# IMU_CAN_Speed_Converter_Board_rev1.net
KiCad netlist of a schematic drawn in EAGLE
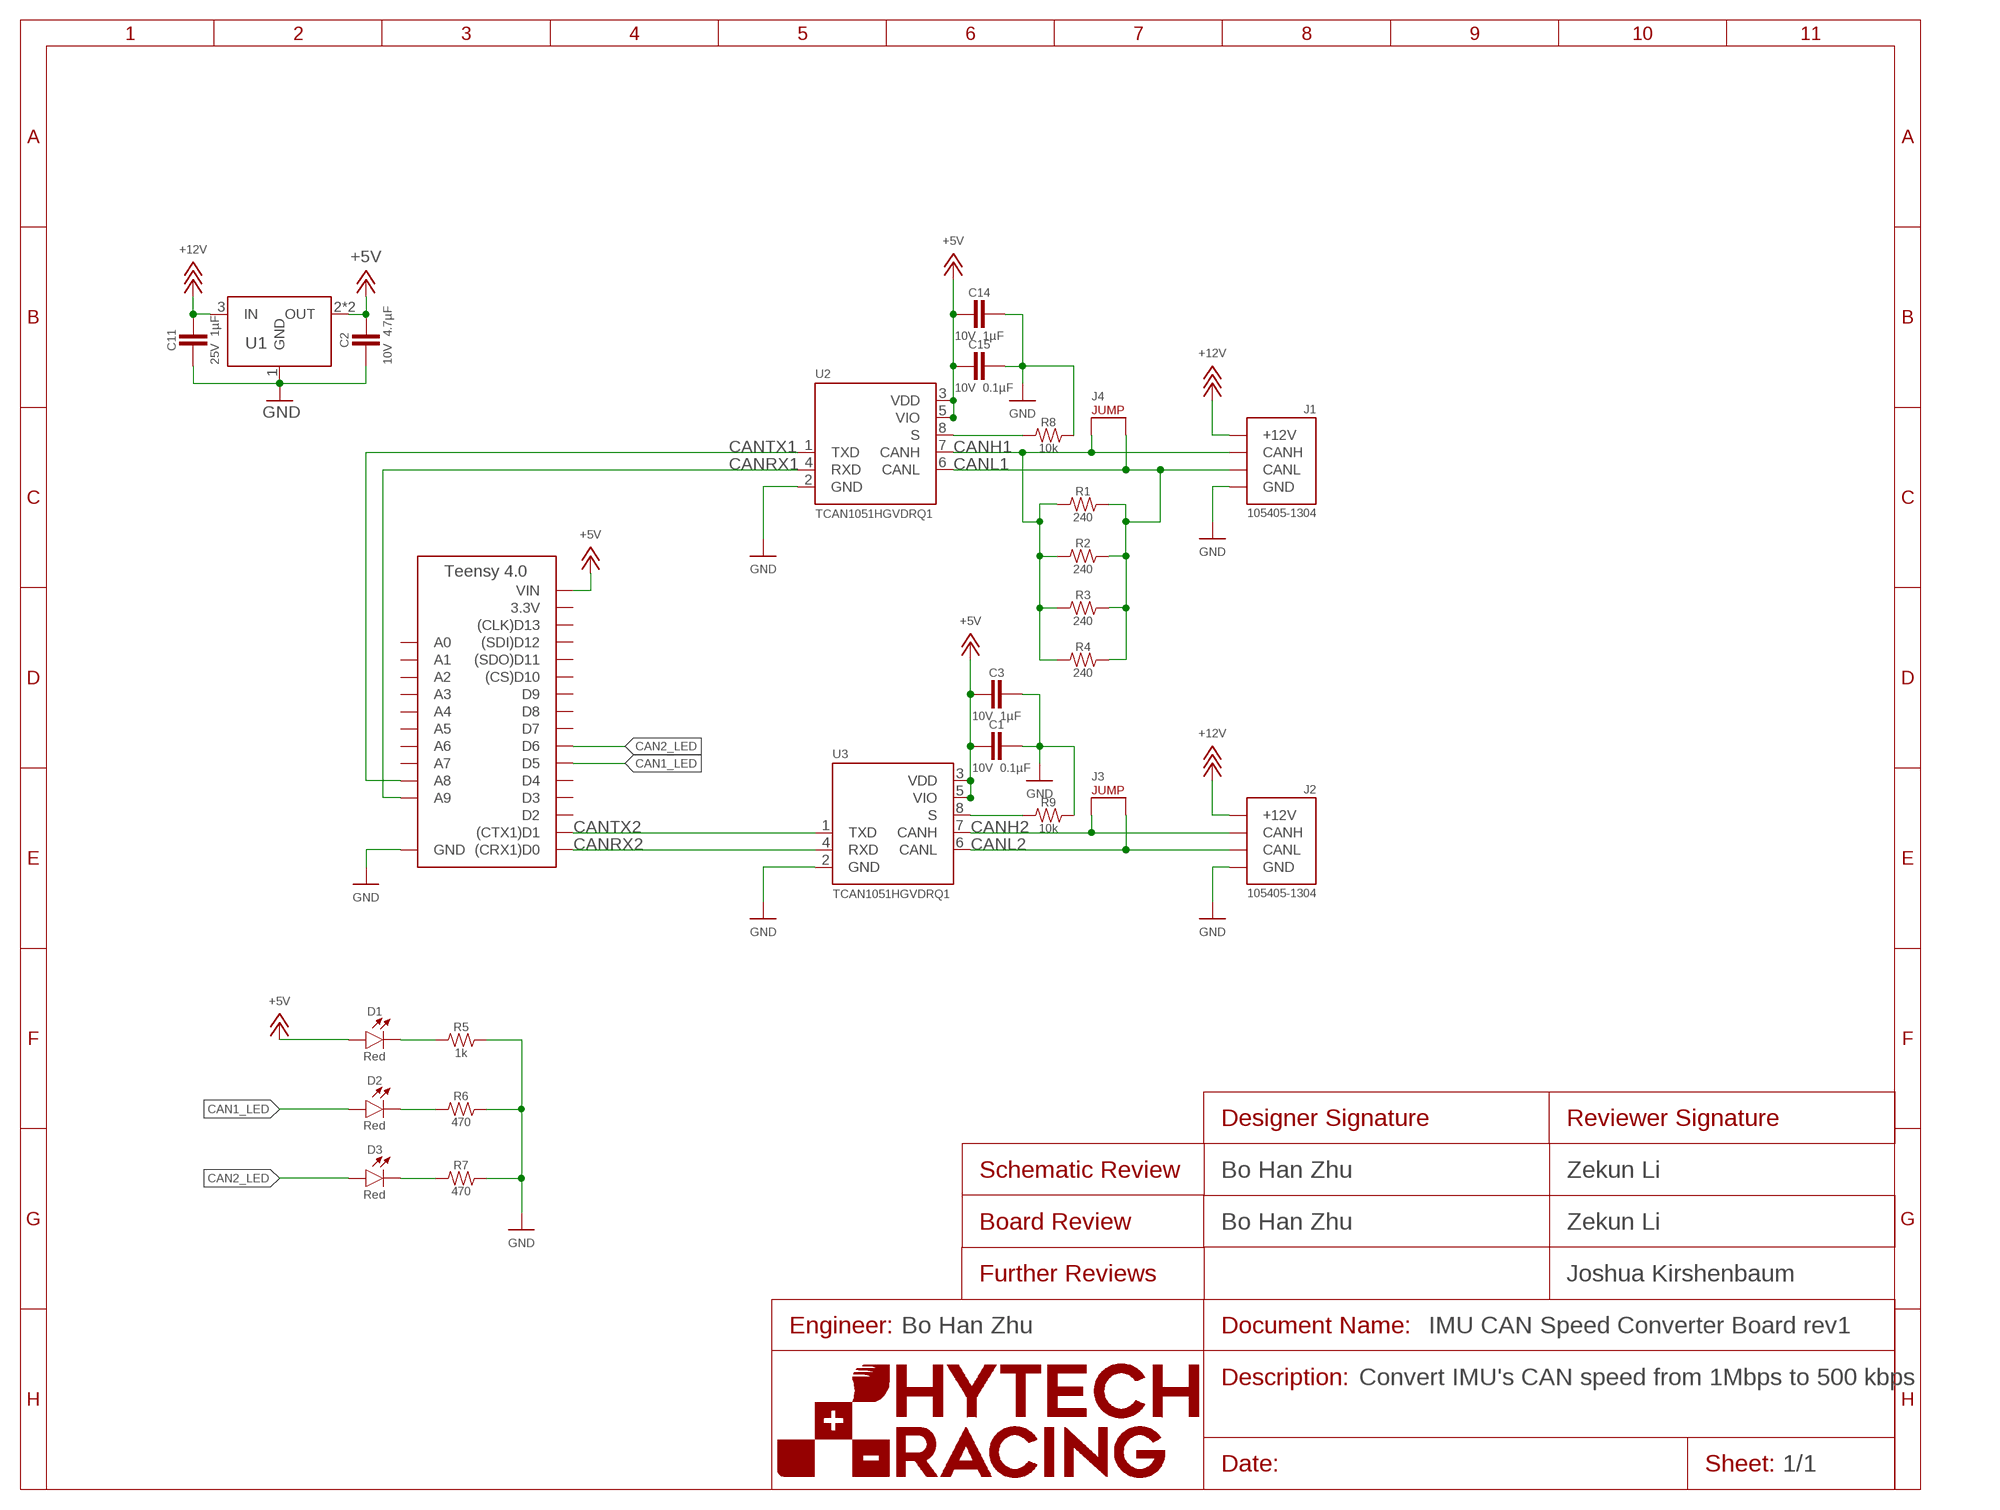
[diagram p0: schematic, sheet 1]

(export (version "E")
  (design (tool "Eeschema 10.0.6"))
  (components
    (comp (ref "A1")
      (value "TEENSY_4.0")
      (footprint "eagle-import:TEENSY_SHORT")
      (libsource (lib "eagle-import") (part "TEENSY_4.0"))
    )
    (comp (ref "C1")
      (value "CAPACITOR_0603_10V_0.1UF")
      (footprint "eagle-import:0603-CAP")
      (fields
        (field (name "CAPACITANCE") "0.1µF")
        (field (name "MANUFACTURER") "Vishay Vitramon")
        (field (name "MPN") "VJ0603Y104JXQPW1BC")
        (field (name "TOLERANCE") "5%")
        (field (name "VOLTAGE") "10V")
      )
      (libsource (lib "eagle-import") (part "CAPACITOR_?_060310V_0.1UF"))
    )
    (comp (ref "C2")
      (value "CAPACITOR_0603_10V_4.7UF")
      (footprint "eagle-import:0603-CAP")
      (fields
        (field (name "CAPACITANCE") "4.7µF")
        (field (name "MANUFACTURER") "Samsung Electro-Mechanics")
        (field (name "MPN") "CL10A475KP8NNNC")
        (field (name "TOLERANCE") "10%")
        (field (name "VOLTAGE") "10V")
      )
      (libsource (lib "eagle-import") (part "CAPACITOR_?_060310V_4.7UF"))
    )
    (comp (ref "C3")
      (value "CAPACITOR_0603_10V_1UF")
      (footprint "eagle-import:0603-CAP")
      (fields
        (field (name "CAPACITANCE") "1µF")
        (field (name "MANUFACTURER") "Yageo")
        (field (name "MPN") "CC0603KRX7R6BB105")
        (field (name "TOLERANCE") "10%")
        (field (name "VOLTAGE") "10V")
      )
      (libsource (lib "eagle-import") (part "CAPACITOR_?_060310V_1UF"))
    )
    (comp (ref "C11")
      (value "CAPACITOR_0603_25V_1UF")
      (footprint "eagle-import:0603-CAP")
      (fields
        (field (name "CAPACITANCE") "1µF")
        (field (name "MANUFACTURER") "Samsung Electro-Mechanics")
        (field (name "MPN") "CL10B105KA8NNNC")
        (field (name "TOLERANCE") "10%")
        (field (name "VOLTAGE") "25V")
      )
      (libsource (lib "eagle-import") (part "CAPACITOR_?_060325V_1UF"))
    )
    (comp (ref "C14")
      (value "CAPACITOR_0603_10V_1UF")
      (footprint "eagle-import:0603-CAP")
      (fields
        (field (name "CAPACITANCE") "1µF")
        (field (name "MANUFACTURER") "Yageo")
        (field (name "MPN") "CC0603KRX7R6BB105")
        (field (name "TOLERANCE") "10%")
        (field (name "VOLTAGE") "10V")
      )
      (libsource (lib "eagle-import") (part "CAPACITOR_?_060310V_1UF"))
    )
    (comp (ref "C15")
      (value "CAPACITOR_0603_10V_0.1UF")
      (footprint "eagle-import:0603-CAP")
      (fields
        (field (name "CAPACITANCE") "0.1µF")
        (field (name "MANUFACTURER") "Vishay Vitramon")
        (field (name "MPN") "VJ0603Y104JXQPW1BC")
        (field (name "TOLERANCE") "5%")
        (field (name "VOLTAGE") "10V")
      )
      (libsource (lib "eagle-import") (part "CAPACITOR_?_060310V_0.1UF"))
    )
    (comp (ref "D1")
      (value "LED_0603_RED")
      (footprint "eagle-import:0603-LED")
      (fields
        (field (name "COLOR") "Red")
        (field (name "MANUFACTURER") "Kingbright")
        (field (name "MPN") "APT1608SECK/J3-PRV")
      )
      (libsource (lib "eagle-import") (part "LED_?_0603RED"))
    )
    (comp (ref "D2")
      (value "LED_0603_RED")
      (footprint "eagle-import:0603-LED")
      (fields
        (field (name "COLOR") "Red")
        (field (name "MANUFACTURER") "Kingbright")
        (field (name "MPN") "APT1608SECK/J3-PRV")
      )
      (libsource (lib "eagle-import") (part "LED_?_0603RED"))
    )
    (comp (ref "D3")
      (value "LED_0603_RED")
      (footprint "eagle-import:0603-LED")
      (fields
        (field (name "COLOR") "Red")
        (field (name "MANUFACTURER") "Kingbright")
        (field (name "MPN") "APT1608SECK/J3-PRV")
      )
      (libsource (lib "eagle-import") (part "LED_?_0603RED"))
    )
    (comp (ref "J1")
      (value "CONNECTOR-CAN_NF_S_RA_BLACK")
      (footprint "eagle-import:MOLEX_NANOFIT_SMD_RIGHTANGLE_04")
      (fields (field (name "MANUFACTURER") "Molex") (field (name "MPN") "105405-1304"))
      (libsource (lib "eagle-import") (part "CONNECTOR-CAN_?_NF_S_RABLACK"))
    )
    (comp (ref "J2")
      (value "CONNECTOR-CAN_NF_S_RA_BLACK")
      (footprint "eagle-import:MOLEX_NANOFIT_SMD_RIGHTANGLE_04")
      (fields (field (name "MANUFACTURER") "Molex") (field (name "MPN") "105405-1304"))
      (libsource (lib "eagle-import") (part "CONNECTOR-CAN_?_NF_S_RABLACK"))
    )
    (comp (ref "J3")
      (value "JUMPER_1X02_")
      (footprint "eagle-import:1X02")
      (libsource (lib "eagle-import") (part "JUMPER_?_1X02"))
    )
    (comp (ref "J4")
      (value "JUMPER_1X02_")
      (footprint "eagle-import:1X02")
      (libsource (lib "eagle-import") (part "JUMPER_?_1X02"))
    )
    (comp (ref "R1")
      (value "RESISTOR_0603_240")
      (footprint "eagle-import:0603-RES")
      (fields
        (field (name "MANUFACTURER") "Yageo")
        (field (name "MPN") "RC0603FR-07240RL")
        (field (name "POWER") "0.1W")
        (field (name "RESISTANCE") "240")
      )
      (libsource (lib "eagle-import") (part "RESISTOR_?_0603240"))
    )
    (comp (ref "R2")
      (value "RESISTOR_0603_240")
      (footprint "eagle-import:0603-RES")
      (fields
        (field (name "MANUFACTURER") "Yageo")
        (field (name "MPN") "RC0603FR-07240RL")
        (field (name "POWER") "0.1W")
        (field (name "RESISTANCE") "240")
      )
      (libsource (lib "eagle-import") (part "RESISTOR_?_0603240"))
    )
    (comp (ref "R3")
      (value "RESISTOR_0603_240")
      (footprint "eagle-import:0603-RES")
      (fields
        (field (name "MANUFACTURER") "Yageo")
        (field (name "MPN") "RC0603FR-07240RL")
        (field (name "POWER") "0.1W")
        (field (name "RESISTANCE") "240")
      )
      (libsource (lib "eagle-import") (part "RESISTOR_?_0603240"))
    )
    (comp (ref "R4")
      (value "RESISTOR_0603_240")
      (footprint "eagle-import:0603-RES")
      (fields
        (field (name "MANUFACTURER") "Yageo")
        (field (name "MPN") "RC0603FR-07240RL")
        (field (name "POWER") "0.1W")
        (field (name "RESISTANCE") "240")
      )
      (libsource (lib "eagle-import") (part "RESISTOR_?_0603240"))
    )
    (comp (ref "R5")
      (value "RESISTOR_0603_1K")
      (footprint "eagle-import:0603-RES")
      (fields
        (field (name "MANUFACTURER") "Yageo")
        (field (name "MPN") "RC0603FR-071KL")
        (field (name "POWER") "0.1W")
        (field (name "RESISTANCE") "1k")
      )
      (libsource (lib "eagle-import") (part "RESISTOR_?_06031K"))
    )
    (comp (ref "R6")
      (value "RESISTOR_0603_470")
      (footprint "eagle-import:0603-RES")
      (fields
        (field (name "MANUFACTURER") "Panasonic Electronic Components")
        (field (name "MPN") "ERJ-PA3F4700V")
        (field (name "POWER") "0.25W")
        (field (name "RESISTANCE") "470")
      )
      (libsource (lib "eagle-import") (part "RESISTOR_?_0603470"))
    )
    (comp (ref "R7")
      (value "RESISTOR_0603_470")
      (footprint "eagle-import:0603-RES")
      (fields
        (field (name "MANUFACTURER") "Panasonic Electronic Components")
        (field (name "MPN") "ERJ-PA3F4700V")
        (field (name "POWER") "0.25W")
        (field (name "RESISTANCE") "470")
      )
      (libsource (lib "eagle-import") (part "RESISTOR_?_0603470"))
    )
    (comp (ref "R8")
      (value "RESISTOR_0603_10K")
      (footprint "eagle-import:0603-RES")
      (fields
        (field (name "MANUFACTURER") "Yageo")
        (field (name "MPN") "RC0603FR-0710KL")
        (field (name "POWER") "0.1W")
        (field (name "RESISTANCE") "10k")
      )
      (libsource (lib "eagle-import") (part "RESISTOR_?_060310K"))
    )
    (comp (ref "R9")
      (value "RESISTOR_0603_10K")
      (footprint "eagle-import:0603-RES")
      (fields
        (field (name "MANUFACTURER") "Yageo")
        (field (name "MPN") "RC0603FR-0710KL")
        (field (name "POWER") "0.1W")
        (field (name "RESISTANCE") "10k")
      )
      (libsource (lib "eagle-import") (part "RESISTOR_?_060310K"))
    )
    (comp (ref "U1")
      (value "VOLTAGE_REGULATOR_SOT223_5V")
      (footprint "eagle-import:SOT223")
      (fields (field (name "MANUFACTURER") "STMicroelectronics") (field (name "MPN") "LDL1117S50R"))
      (libsource (lib "eagle-import") (part "VOLTAGE_REGULATOR_?_SOT2235V"))
    )
    (comp (ref "U2")
      (value "TCAN1051HQV-Q1")
      (footprint "eagle-import:SOIC-08(NARROW,0.15_)")
      (fields (field (name "MANUFACTURER") "Texas Instruments") (field (name "MPN") "TCAN1051HGVDRQ1"))
      (libsource (lib "eagle-import") (part "TCAN1051V-Q1HQ"))
    )
    (comp (ref "U3")
      (value "TCAN1051HQV-Q1")
      (footprint "eagle-import:SOIC-08(NARROW,0.15_)")
      (fields (field (name "MANUFACTURER") "Texas Instruments") (field (name "MPN") "TCAN1051HGVDRQ1"))
      (libsource (lib "eagle-import") (part "TCAN1051V-Q1HQ"))
    )
  )
  (nets
    (net (code "1") (name "+5V") (class "Default")
      (node (ref "A1") (pin "VIN") (pinfunction "VIN_VIN") (pintype "power_in"))
      (node (ref "C1") (pin "2") (pinfunction "2_2") (pintype "passive"))
      (node (ref "C14") (pin "2") (pinfunction "2_2") (pintype "passive"))
      (node (ref "C15") (pin "2") (pinfunction "2_2") (pintype "passive"))
      (node (ref "C2") (pin "1") (pinfunction "1_1") (pintype "passive"))
      (node (ref "C3") (pin "2") (pinfunction "2_2") (pintype "passive"))
      (node (ref "D1") (pin "2") (pinfunction "A_2") (pintype "passive"))
      (node (ref "U1") (pin "2") (pinfunction "OUT_2") (pintype "power_in"))
      (node (ref "U1") (pin "4") (pinfunction "OUT_4") (pintype "power_in"))
      (node (ref "U2") (pin "3") (pinfunction "VDD_3") (pintype "power_in"))
      (node (ref "U2") (pin "5") (pinfunction "VIO_5") (pintype "power_in"))
      (node (ref "U3") (pin "3") (pinfunction "VDD_3") (pintype "power_in"))
      (node (ref "U3") (pin "5") (pinfunction "VIO_5") (pintype "power_in"))
    )
    (net (code "2") (name "+12V") (class "Default")
      (node (ref "C11") (pin "1") (pinfunction "1_1") (pintype "passive"))
      (node (ref "J1") (pin "1") (pinfunction "+12V_1") (pintype "power_in"))
      (node (ref "J2") (pin "1") (pinfunction "+12V_1") (pintype "power_in"))
      (node (ref "U1") (pin "3") (pinfunction "IN_3") (pintype "power_in"))
    )
    (net (code "3") (name "/3.3V") (class "Default")
      (node (ref "A1") (pin "3.3V") (pinfunction "3.3V_3.3V") (pintype "power_in"))
    )
    (net (code "4") (name "/CANH1") (class "Default")
      (node (ref "J1") (pin "4") (pinfunction "CANH_4") (pintype "bidirectional"))
      (node (ref "J4") (pin "1") (pinfunction "P$1_1") (pintype "passive"))
      (node (ref "R1") (pin "1") (pinfunction "1_1") (pintype "passive"))
      (node (ref "R2") (pin "1") (pinfunction "1_1") (pintype "passive"))
      (node (ref "R3") (pin "1") (pinfunction "1_1") (pintype "passive"))
      (node (ref "R4") (pin "1") (pinfunction "1_1") (pintype "passive"))
      (node (ref "U2") (pin "7") (pinfunction "CANH_7") (pintype "output"))
    )
    (net (code "5") (name "/CANH2") (class "Default")
      (node (ref "J2") (pin "4") (pinfunction "CANH_4") (pintype "bidirectional"))
      (node (ref "J3") (pin "1") (pinfunction "P$1_1") (pintype "passive"))
      (node (ref "U3") (pin "7") (pinfunction "CANH_7") (pintype "output"))
    )
    (net (code "6") (name "/CANL1") (class "Default")
      (node (ref "J1") (pin "3") (pinfunction "CANL_3") (pintype "bidirectional"))
      (node (ref "J4") (pin "2") (pinfunction "P$2_2") (pintype "passive"))
      (node (ref "R1") (pin "2") (pinfunction "2_2") (pintype "passive"))
      (node (ref "R2") (pin "2") (pinfunction "2_2") (pintype "passive"))
      (node (ref "R3") (pin "2") (pinfunction "2_2") (pintype "passive"))
      (node (ref "R4") (pin "2") (pinfunction "2_2") (pintype "passive"))
      (node (ref "U2") (pin "6") (pinfunction "CANL_6") (pintype "bidirectional"))
    )
    (net (code "7") (name "/CANL2") (class "Default")
      (node (ref "J2") (pin "3") (pinfunction "CANL_3") (pintype "bidirectional"))
      (node (ref "J3") (pin "2") (pinfunction "P$2_2") (pintype "passive"))
      (node (ref "U3") (pin "6") (pinfunction "CANL_6") (pintype "bidirectional"))
    )
    (net (code "8") (name "/CANRX1") (class "Default")
      (node (ref "A1") (pin "D23") (pinfunction "A9_D23") (pintype "bidirectional"))
      (node (ref "U2") (pin "4") (pinfunction "RXD_4") (pintype "output"))
    )
    (net (code "9") (name "/CANRX2") (class "Default")
      (node (ref "A1") (pin "D0") (pinfunction "(CRX1)D0_D0") (pintype "bidirectional"))
      (node (ref "U3") (pin "4") (pinfunction "RXD_4") (pintype "output"))
    )
    (net (code "10") (name "/CANTX1") (class "Default")
      (node (ref "A1") (pin "D22") (pinfunction "A8_D22") (pintype "bidirectional"))
      (node (ref "U2") (pin "1") (pinfunction "TXD_1") (pintype "input"))
    )
    (net (code "11") (name "/CANTX2") (class "Default")
      (node (ref "A1") (pin "D1") (pinfunction "(CTX1)D1_D1") (pintype "bidirectional"))
      (node (ref "U3") (pin "1") (pinfunction "TXD_1") (pintype "input"))
    )
    (net (code "12") (name "CAN1_LED") (class "Default")
      (node (ref "A1") (pin "D5") (pinfunction "D5_D5") (pintype "bidirectional"))
      (node (ref "D2") (pin "2") (pinfunction "A_2") (pintype "passive"))
    )
    (net (code "13") (name "CAN2_LED") (class "Default")
      (node (ref "A1") (pin "D6") (pinfunction "D6_D6") (pintype "bidirectional"))
      (node (ref "D3") (pin "2") (pinfunction "A_2") (pintype "passive"))
    )
    (net (code "14") (name "GND") (class "Default")
      (node (ref "A1") (pin "AGND/GND") (pinfunction "GND_AGND/GND") (pintype "power_in"))
      (node (ref "A1") (pin "GND") (pinfunction "GND_GND") (pintype "power_in"))
      (node (ref "C1") (pin "1") (pinfunction "1_1") (pintype "passive"))
      (node (ref "C11") (pin "2") (pinfunction "2_2") (pintype "passive"))
      (node (ref "C14") (pin "1") (pinfunction "1_1") (pintype "passive"))
      (node (ref "C15") (pin "1") (pinfunction "1_1") (pintype "passive"))
      (node (ref "C2") (pin "2") (pinfunction "2_2") (pintype "passive"))
      (node (ref "C3") (pin "1") (pinfunction "1_1") (pintype "passive"))
      (node (ref "J1") (pin "2") (pinfunction "GND_2") (pintype "power_in"))
      (node (ref "J2") (pin "2") (pinfunction "GND_2") (pintype "power_in"))
      (node (ref "R5") (pin "2") (pinfunction "2_2") (pintype "passive"))
      (node (ref "R6") (pin "2") (pinfunction "2_2") (pintype "passive"))
      (node (ref "R7") (pin "2") (pinfunction "2_2") (pintype "passive"))
      (node (ref "R8") (pin "2") (pinfunction "2_2") (pintype "passive"))
      (node (ref "R9") (pin "2") (pinfunction "2_2") (pintype "passive"))
      (node (ref "U1") (pin "1") (pinfunction "GND_1") (pintype "power_in"))
      (node (ref "U2") (pin "2") (pinfunction "GND_2") (pintype "power_in"))
      (node (ref "U3") (pin "2") (pinfunction "GND_2") (pintype "power_in"))
    )
    (net (code "15") (name "Net-(D1-C)") (class "Default")
      (node (ref "D1") (pin "1") (pinfunction "C_1") (pintype "passive"))
      (node (ref "R5") (pin "1") (pinfunction "1_1") (pintype "passive"))
    )
    (net (code "16") (name "Net-(D2-C)") (class "Default")
      (node (ref "D2") (pin "1") (pinfunction "C_1") (pintype "passive"))
      (node (ref "R6") (pin "1") (pinfunction "1_1") (pintype "passive"))
    )
    (net (code "17") (name "Net-(D3-C)") (class "Default")
      (node (ref "D3") (pin "1") (pinfunction "C_1") (pintype "passive"))
      (node (ref "R7") (pin "1") (pinfunction "1_1") (pintype "passive"))
    )
    (net (code "18") (name "Net-(U2-S)") (class "Default")
      (node (ref "R8") (pin "1") (pinfunction "1_1") (pintype "passive"))
      (node (ref "U2") (pin "8") (pinfunction "S_8") (pintype "input"))
    )
    (net (code "19") (name "Net-(U3-S)") (class "Default")
      (node (ref "R9") (pin "1") (pinfunction "1_1") (pintype "passive"))
      (node (ref "U3") (pin "8") (pinfunction "S_8") (pintype "input"))
    )
    (net (code "20") (name "unconnected-(A1-(CLK)D13-PadD13)") (class "Default")
      (node (ref "A1") (pin "D13") (pinfunction "(CLK)D13_D13") (pintype "bidirectional"))
    )
    (net (code "21") (name "unconnected-(A1-(CS)D10-PadD10)") (class "Default")
      (node (ref "A1") (pin "D10") (pinfunction "(CS)D10_D10") (pintype "bidirectional"))
    )
    (net (code "22") (name "unconnected-(A1-(SDI)D12-PadD12)") (class "Default")
      (node (ref "A1") (pin "D12") (pinfunction "(SDI)D12_D12") (pintype "bidirectional"))
    )
    (net (code "23") (name "unconnected-(A1-(SDO)D11-PadD11)") (class "Default")
      (node (ref "A1") (pin "D11") (pinfunction "(SDO)D11_D11") (pintype "bidirectional"))
    )
    (net (code "24") (name "unconnected-(A1-A0-PadD14)") (class "Default")
      (node (ref "A1") (pin "D14") (pinfunction "A0_D14") (pintype "bidirectional"))
    )
    (net (code "25") (name "unconnected-(A1-A1-PadD15)") (class "Default")
      (node (ref "A1") (pin "D15") (pinfunction "A1_D15") (pintype "bidirectional"))
    )
    (net (code "26") (name "unconnected-(A1-A2-PadD16)") (class "Default")
      (node (ref "A1") (pin "D16") (pinfunction "A2_D16") (pintype "bidirectional"))
    )
    (net (code "27") (name "unconnected-(A1-A3-PadD17)") (class "Default")
      (node (ref "A1") (pin "D17") (pinfunction "A3_D17") (pintype "bidirectional"))
    )
    (net (code "28") (name "unconnected-(A1-A4-PadD18)") (class "Default")
      (node (ref "A1") (pin "D18") (pinfunction "A4_D18") (pintype "bidirectional"))
    )
    (net (code "29") (name "unconnected-(A1-A5-PadD19)") (class "Default")
      (node (ref "A1") (pin "D19") (pinfunction "A5_D19") (pintype "bidirectional"))
    )
    (net (code "30") (name "unconnected-(A1-A6-PadD20)") (class "Default")
      (node (ref "A1") (pin "D20") (pinfunction "A6_D20") (pintype "bidirectional"))
    )
    (net (code "31") (name "unconnected-(A1-A7-PadD21)") (class "Default")
      (node (ref "A1") (pin "D21") (pinfunction "A7_D21") (pintype "bidirectional"))
    )
    (net (code "32") (name "unconnected-(A1-PadD2)") (class "Default")
      (node (ref "A1") (pin "D2") (pinfunction "D2_D2") (pintype "bidirectional"))
    )
    (net (code "33") (name "unconnected-(A1-PadD3)") (class "Default")
      (node (ref "A1") (pin "D3") (pinfunction "D3_D3") (pintype "bidirectional"))
    )
    (net (code "34") (name "unconnected-(A1-PadD4)") (class "Default")
      (node (ref "A1") (pin "D4") (pinfunction "D4_D4") (pintype "bidirectional"))
    )
    (net (code "35") (name "unconnected-(A1-PadD7)") (class "Default")
      (node (ref "A1") (pin "D7") (pinfunction "D7_D7") (pintype "bidirectional"))
    )
    (net (code "36") (name "unconnected-(A1-PadD8)") (class "Default")
      (node (ref "A1") (pin "D8") (pinfunction "D8_D8") (pintype "bidirectional"))
    )
    (net (code "37") (name "unconnected-(A1-PadD9)") (class "Default")
      (node (ref "A1") (pin "D9") (pinfunction "D9_D9") (pintype "bidirectional"))
    )
  )
)
